# Motor_Controller.net
KiCad netlist of a schematic drawn in EAGLE
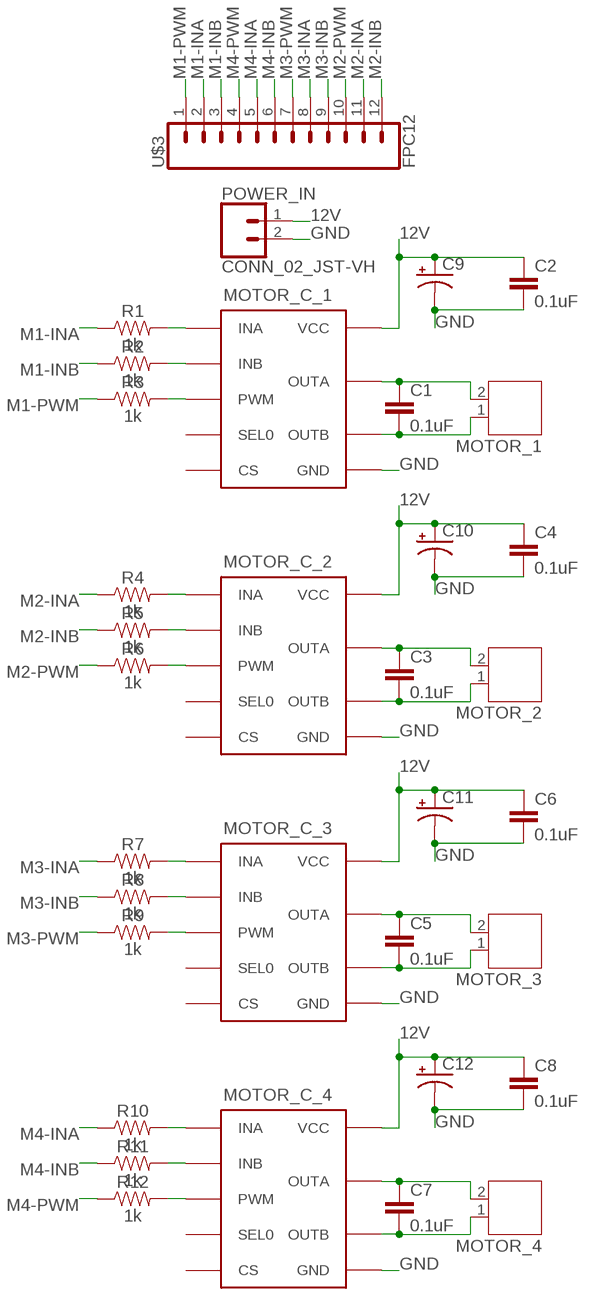
[diagram p0: schematic, sheet 1]

(export (version "E")
  (design (tool "Eeschema 10.0.6"))
  (components
    (comp (ref "C1")
      (value "0.1uF")
      (footprint "eagle-import:0603")
      (libsource (lib "eagle-import") (part "0.1UF-0603-25V-(+80/-20%)"))
    )
    (comp (ref "C2")
      (value "0.1uF")
      (footprint "eagle-import:0603")
      (libsource (lib "eagle-import") (part "0.1UF-0603-25V-(+80/-20%)"))
    )
    (comp (ref "C3")
      (value "0.1uF")
      (footprint "eagle-import:0603")
      (libsource (lib "eagle-import") (part "0.1UF-0603-25V-(+80/-20%)"))
    )
    (comp (ref "C4")
      (value "0.1uF")
      (footprint "eagle-import:0603")
      (libsource (lib "eagle-import") (part "0.1UF-0603-25V-(+80/-20%)"))
    )
    (comp (ref "C5")
      (value "0.1uF")
      (footprint "eagle-import:0603")
      (libsource (lib "eagle-import") (part "0.1UF-0603-25V-(+80/-20%)"))
    )
    (comp (ref "C6")
      (value "0.1uF")
      (footprint "eagle-import:0603")
      (libsource (lib "eagle-import") (part "0.1UF-0603-25V-(+80/-20%)"))
    )
    (comp (ref "C7")
      (value "0.1uF")
      (footprint "eagle-import:0603")
      (libsource (lib "eagle-import") (part "0.1UF-0603-25V-(+80/-20%)"))
    )
    (comp (ref "C8")
      (value "0.1uF")
      (footprint "eagle-import:0603")
      (libsource (lib "eagle-import") (part "0.1UF-0603-25V-(+80/-20%)"))
    )
    (comp (ref "C9")
      (value "CPOL-USE3.5-8")
      (footprint "eagle-import:E3,5-8")
      (libsource (lib "eagle-import") (part "CPOL-USE3.5-8"))
    )
    (comp (ref "C10")
      (value "CPOL-USE3.5-8")
      (footprint "eagle-import:E3,5-8")
      (libsource (lib "eagle-import") (part "CPOL-USE3.5-8"))
    )
    (comp (ref "C11")
      (value "CPOL-USE3.5-8")
      (footprint "eagle-import:E3,5-8")
      (libsource (lib "eagle-import") (part "CPOL-USE3.5-8"))
    )
    (comp (ref "C12")
      (value "CPOL-USE3.5-8")
      (footprint "eagle-import:E3,5-8")
      (libsource (lib "eagle-import") (part "CPOL-USE3.5-8"))
    )
    (comp (ref "MOTOR_1")
      (value "JST-PH2")
      (footprint "eagle-import:JST-PH2")
      (libsource (lib "eagle-import") (part "JST-PH2"))
    )
    (comp (ref "MOTOR_2")
      (value "JST-PH2")
      (footprint "eagle-import:JST-PH2")
      (libsource (lib "eagle-import") (part "JST-PH2"))
    )
    (comp (ref "MOTOR_3")
      (value "JST-PH2")
      (footprint "eagle-import:JST-PH2")
      (libsource (lib "eagle-import") (part "JST-PH2"))
    )
    (comp (ref "MOTOR_4")
      (value "JST-PH2")
      (footprint "eagle-import:JST-PH2")
      (libsource (lib "eagle-import") (part "JST-PH2"))
    )
    (comp (ref "MOTOR_C_1")
      (value "VNH7100BASTR")
      (footprint "eagle-import:SO-16")
      (libsource (lib "eagle-import") (part "VNH7100BASTR"))
    )
    (comp (ref "MOTOR_C_2")
      (value "VNH7100BASTR")
      (footprint "eagle-import:SO-16")
      (libsource (lib "eagle-import") (part "VNH7100BASTR"))
    )
    (comp (ref "MOTOR_C_3")
      (value "VNH7100BASTR")
      (footprint "eagle-import:SO-16")
      (libsource (lib "eagle-import") (part "VNH7100BASTR"))
    )
    (comp (ref "MOTOR_C_4")
      (value "VNH7100BASTR")
      (footprint "eagle-import:SO-16")
      (libsource (lib "eagle-import") (part "VNH7100BASTR"))
    )
    (comp (ref "POWER_IN")
      (value "CONN_02_JST-VH")
      (footprint "eagle-import:B2P-VH")
      (libsource (lib "eagle-import") (part "CONN_02_JST-VH"))
    )
    (comp (ref "R1")
      (value "1k")
      (footprint "eagle-import:0603")
      (libsource (lib "eagle-import") (part "1KOHM-0603-1/10W-1%"))
    )
    (comp (ref "R2")
      (value "1k")
      (footprint "eagle-import:0603")
      (libsource (lib "eagle-import") (part "1KOHM-0603-1/10W-1%"))
    )
    (comp (ref "R3")
      (value "1k")
      (footprint "eagle-import:0603")
      (libsource (lib "eagle-import") (part "1KOHM-0603-1/10W-1%"))
    )
    (comp (ref "R4")
      (value "1k")
      (footprint "eagle-import:0603")
      (libsource (lib "eagle-import") (part "1KOHM-0603-1/10W-1%"))
    )
    (comp (ref "R5")
      (value "1k")
      (footprint "eagle-import:0603")
      (libsource (lib "eagle-import") (part "1KOHM-0603-1/10W-1%"))
    )
    (comp (ref "R6")
      (value "1k")
      (footprint "eagle-import:0603")
      (libsource (lib "eagle-import") (part "1KOHM-0603-1/10W-1%"))
    )
    (comp (ref "R7")
      (value "1k")
      (footprint "eagle-import:0603")
      (libsource (lib "eagle-import") (part "1KOHM-0603-1/10W-1%"))
    )
    (comp (ref "R8")
      (value "1k")
      (footprint "eagle-import:0603")
      (libsource (lib "eagle-import") (part "1KOHM-0603-1/10W-1%"))
    )
    (comp (ref "R9")
      (value "1k")
      (footprint "eagle-import:0603")
      (libsource (lib "eagle-import") (part "1KOHM-0603-1/10W-1%"))
    )
    (comp (ref "R10")
      (value "1k")
      (footprint "eagle-import:0603")
      (libsource (lib "eagle-import") (part "1KOHM-0603-1/10W-1%"))
    )
    (comp (ref "R11")
      (value "1k")
      (footprint "eagle-import:0603")
      (libsource (lib "eagle-import") (part "1KOHM-0603-1/10W-1%"))
    )
    (comp (ref "R12")
      (value "1k")
      (footprint "eagle-import:0603")
      (libsource (lib "eagle-import") (part "1KOHM-0603-1/10W-1%"))
    )
    (comp (ref "U$3")
      (value "FPC12")
      (footprint "eagle-import:FPC12")
      (libsource (lib "eagle-import") (part "FPC12"))
    )
  )
  (nets
    (net (code "1") (name "/12V") (class "Default")
      (node (ref "C10") (pin "+") (pinfunction "+_+") (pintype "passive"))
      (node (ref "C11") (pin "+") (pinfunction "+_+") (pintype "passive"))
      (node (ref "C12") (pin "+") (pinfunction "+_+") (pintype "passive"))
      (node (ref "C2") (pin "1") (pinfunction "1_1") (pintype "passive"))
      (node (ref "C4") (pin "1") (pinfunction "1_1") (pintype "passive"))
      (node (ref "C6") (pin "1") (pinfunction "1_1") (pintype "passive"))
      (node (ref "C8") (pin "1") (pinfunction "1_1") (pintype "passive"))
      (node (ref "C9") (pin "+") (pinfunction "+_+") (pintype "passive"))
      (node (ref "MOTOR_C_1") (pin "12") (pinfunction "VCC_12") (pintype "bidirectional"))
      (node (ref "MOTOR_C_1") (pin "4") (pinfunction "VCC_4") (pintype "bidirectional"))
      (node (ref "MOTOR_C_1") (pin "5") (pinfunction "VCC_5") (pintype "bidirectional"))
      (node (ref "MOTOR_C_2") (pin "12") (pinfunction "VCC_12") (pintype "bidirectional"))
      (node (ref "MOTOR_C_2") (pin "4") (pinfunction "VCC_4") (pintype "bidirectional"))
      (node (ref "MOTOR_C_2") (pin "5") (pinfunction "VCC_5") (pintype "bidirectional"))
      (node (ref "MOTOR_C_3") (pin "12") (pinfunction "VCC_12") (pintype "bidirectional"))
      (node (ref "MOTOR_C_3") (pin "4") (pinfunction "VCC_4") (pintype "bidirectional"))
      (node (ref "MOTOR_C_3") (pin "5") (pinfunction "VCC_5") (pintype "bidirectional"))
      (node (ref "MOTOR_C_4") (pin "12") (pinfunction "VCC_12") (pintype "bidirectional"))
      (node (ref "MOTOR_C_4") (pin "4") (pinfunction "VCC_4") (pintype "bidirectional"))
      (node (ref "MOTOR_C_4") (pin "5") (pinfunction "VCC_5") (pintype "bidirectional"))
      (node (ref "POWER_IN") (pin "1") (pinfunction "1_1") (pintype "passive"))
    )
    (net (code "2") (name "/GND") (class "Default")
      (node (ref "C10") (pin "-") (pinfunction "-_-") (pintype "passive"))
      (node (ref "C11") (pin "-") (pinfunction "-_-") (pintype "passive"))
      (node (ref "C12") (pin "-") (pinfunction "-_-") (pintype "passive"))
      (node (ref "C2") (pin "2") (pinfunction "2_2") (pintype "passive"))
      (node (ref "C4") (pin "2") (pinfunction "2_2") (pintype "passive"))
      (node (ref "C6") (pin "2") (pinfunction "2_2") (pintype "passive"))
      (node (ref "C8") (pin "2") (pinfunction "2_2") (pintype "passive"))
      (node (ref "C9") (pin "-") (pinfunction "-_-") (pintype "passive"))
      (node (ref "MOTOR_C_1") (pin "1") (pinfunction "GND_1") (pintype "bidirectional"))
      (node (ref "MOTOR_C_1") (pin "16") (pinfunction "GND_16") (pintype "bidirectional"))
      (node (ref "MOTOR_C_1") (pin "8") (pinfunction "GND_8") (pintype "bidirectional"))
      (node (ref "MOTOR_C_1") (pin "9") (pinfunction "GND_9") (pintype "bidirectional"))
      (node (ref "MOTOR_C_2") (pin "1") (pinfunction "GND_1") (pintype "bidirectional"))
      (node (ref "MOTOR_C_2") (pin "16") (pinfunction "GND_16") (pintype "bidirectional"))
      (node (ref "MOTOR_C_2") (pin "8") (pinfunction "GND_8") (pintype "bidirectional"))
      (node (ref "MOTOR_C_2") (pin "9") (pinfunction "GND_9") (pintype "bidirectional"))
      (node (ref "MOTOR_C_3") (pin "1") (pinfunction "GND_1") (pintype "bidirectional"))
      (node (ref "MOTOR_C_3") (pin "16") (pinfunction "GND_16") (pintype "bidirectional"))
      (node (ref "MOTOR_C_3") (pin "8") (pinfunction "GND_8") (pintype "bidirectional"))
      (node (ref "MOTOR_C_3") (pin "9") (pinfunction "GND_9") (pintype "bidirectional"))
      (node (ref "MOTOR_C_4") (pin "1") (pinfunction "GND_1") (pintype "bidirectional"))
      (node (ref "MOTOR_C_4") (pin "16") (pinfunction "GND_16") (pintype "bidirectional"))
      (node (ref "MOTOR_C_4") (pin "8") (pinfunction "GND_8") (pintype "bidirectional"))
      (node (ref "MOTOR_C_4") (pin "9") (pinfunction "GND_9") (pintype "bidirectional"))
      (node (ref "POWER_IN") (pin "2") (pinfunction "2_2") (pintype "passive"))
    )
    (net (code "3") (name "/M1-INA") (class "Default")
      (node (ref "R1") (pin "1") (pinfunction "1_1") (pintype "passive"))
      (node (ref "U$3") (pin "2") (pinfunction "2_2") (pintype "passive"))
    )
    (net (code "4") (name "/M1-INB") (class "Default")
      (node (ref "R2") (pin "1") (pinfunction "1_1") (pintype "passive"))
      (node (ref "U$3") (pin "3") (pinfunction "3_3") (pintype "passive"))
    )
    (net (code "5") (name "/M1-PWM") (class "Default")
      (node (ref "R3") (pin "1") (pinfunction "1_1") (pintype "passive"))
      (node (ref "U$3") (pin "1") (pinfunction "1_1") (pintype "passive"))
    )
    (net (code "6") (name "/M2-INA") (class "Default")
      (node (ref "R4") (pin "1") (pinfunction "1_1") (pintype "passive"))
      (node (ref "U$3") (pin "11") (pinfunction "11_11") (pintype "passive"))
    )
    (net (code "7") (name "/M2-INB") (class "Default")
      (node (ref "R5") (pin "1") (pinfunction "1_1") (pintype "passive"))
      (node (ref "U$3") (pin "12") (pinfunction "12_12") (pintype "passive"))
    )
    (net (code "8") (name "/M2-PWM") (class "Default")
      (node (ref "R6") (pin "1") (pinfunction "1_1") (pintype "passive"))
      (node (ref "U$3") (pin "10") (pinfunction "10_10") (pintype "passive"))
    )
    (net (code "9") (name "/M3-INA") (class "Default")
      (node (ref "R7") (pin "1") (pinfunction "1_1") (pintype "passive"))
      (node (ref "U$3") (pin "8") (pinfunction "8_8") (pintype "passive"))
    )
    (net (code "10") (name "/M3-INB") (class "Default")
      (node (ref "R8") (pin "1") (pinfunction "1_1") (pintype "passive"))
      (node (ref "U$3") (pin "9") (pinfunction "9_9") (pintype "passive"))
    )
    (net (code "11") (name "/M3-PWM") (class "Default")
      (node (ref "R9") (pin "1") (pinfunction "1_1") (pintype "passive"))
      (node (ref "U$3") (pin "7") (pinfunction "7_7") (pintype "passive"))
    )
    (net (code "12") (name "/M4-INA") (class "Default")
      (node (ref "R10") (pin "1") (pinfunction "1_1") (pintype "passive"))
      (node (ref "U$3") (pin "5") (pinfunction "5_5") (pintype "passive"))
    )
    (net (code "13") (name "/M4-INB") (class "Default")
      (node (ref "R11") (pin "1") (pinfunction "1_1") (pintype "passive"))
      (node (ref "U$3") (pin "6") (pinfunction "6_6") (pintype "passive"))
    )
    (net (code "14") (name "/M4-PWM") (class "Default")
      (node (ref "R12") (pin "1") (pinfunction "1_1") (pintype "passive"))
      (node (ref "U$3") (pin "4") (pinfunction "4_4") (pintype "passive"))
    )
    (net (code "15") (name "Net-(C1-Pad1)") (class "Default")
      (node (ref "C1") (pin "1") (pinfunction "1_1") (pintype "passive"))
      (node (ref "MOTOR_1") (pin "2") (pinfunction "2_2") (pintype "passive"))
      (node (ref "MOTOR_C_1") (pin "15") (pinfunction "OUTA_15") (pintype "bidirectional"))
      (node (ref "MOTOR_C_1") (pin "2") (pinfunction "OUTA_2") (pintype "bidirectional"))
    )
    (net (code "16") (name "Net-(C1-Pad2)") (class "Default")
      (node (ref "C1") (pin "2") (pinfunction "2_2") (pintype "passive"))
      (node (ref "MOTOR_1") (pin "1") (pinfunction "1_1") (pintype "passive"))
      (node (ref "MOTOR_C_1") (pin "10") (pinfunction "OUTB_10") (pintype "bidirectional"))
      (node (ref "MOTOR_C_1") (pin "7") (pinfunction "OUTB_7") (pintype "bidirectional"))
    )
    (net (code "17") (name "Net-(C3-Pad1)") (class "Default")
      (node (ref "C3") (pin "1") (pinfunction "1_1") (pintype "passive"))
      (node (ref "MOTOR_2") (pin "2") (pinfunction "2_2") (pintype "passive"))
      (node (ref "MOTOR_C_2") (pin "15") (pinfunction "OUTA_15") (pintype "bidirectional"))
      (node (ref "MOTOR_C_2") (pin "2") (pinfunction "OUTA_2") (pintype "bidirectional"))
    )
    (net (code "18") (name "Net-(C3-Pad2)") (class "Default")
      (node (ref "C3") (pin "2") (pinfunction "2_2") (pintype "passive"))
      (node (ref "MOTOR_2") (pin "1") (pinfunction "1_1") (pintype "passive"))
      (node (ref "MOTOR_C_2") (pin "10") (pinfunction "OUTB_10") (pintype "bidirectional"))
      (node (ref "MOTOR_C_2") (pin "7") (pinfunction "OUTB_7") (pintype "bidirectional"))
    )
    (net (code "19") (name "Net-(C5-Pad1)") (class "Default")
      (node (ref "C5") (pin "1") (pinfunction "1_1") (pintype "passive"))
      (node (ref "MOTOR_3") (pin "2") (pinfunction "2_2") (pintype "passive"))
      (node (ref "MOTOR_C_3") (pin "15") (pinfunction "OUTA_15") (pintype "bidirectional"))
      (node (ref "MOTOR_C_3") (pin "2") (pinfunction "OUTA_2") (pintype "bidirectional"))
    )
    (net (code "20") (name "Net-(C5-Pad2)") (class "Default")
      (node (ref "C5") (pin "2") (pinfunction "2_2") (pintype "passive"))
      (node (ref "MOTOR_3") (pin "1") (pinfunction "1_1") (pintype "passive"))
      (node (ref "MOTOR_C_3") (pin "10") (pinfunction "OUTB_10") (pintype "bidirectional"))
      (node (ref "MOTOR_C_3") (pin "7") (pinfunction "OUTB_7") (pintype "bidirectional"))
    )
    (net (code "21") (name "Net-(C7-Pad1)") (class "Default")
      (node (ref "C7") (pin "1") (pinfunction "1_1") (pintype "passive"))
      (node (ref "MOTOR_4") (pin "2") (pinfunction "2_2") (pintype "passive"))
      (node (ref "MOTOR_C_4") (pin "15") (pinfunction "OUTA_15") (pintype "bidirectional"))
      (node (ref "MOTOR_C_4") (pin "2") (pinfunction "OUTA_2") (pintype "bidirectional"))
    )
    (net (code "22") (name "Net-(C7-Pad2)") (class "Default")
      (node (ref "C7") (pin "2") (pinfunction "2_2") (pintype "passive"))
      (node (ref "MOTOR_4") (pin "1") (pinfunction "1_1") (pintype "passive"))
      (node (ref "MOTOR_C_4") (pin "10") (pinfunction "OUTB_10") (pintype "bidirectional"))
      (node (ref "MOTOR_C_4") (pin "7") (pinfunction "OUTB_7") (pintype "bidirectional"))
    )
    (net (code "23") (name "Net-(MOTOR_C_1-INA)") (class "Default")
      (node (ref "MOTOR_C_1") (pin "3") (pinfunction "INA_3") (pintype "bidirectional"))
      (node (ref "R1") (pin "2") (pinfunction "2_2") (pintype "passive"))
    )
    (net (code "24") (name "Net-(MOTOR_C_1-INB)") (class "Default")
      (node (ref "MOTOR_C_1") (pin "6") (pinfunction "INB_6") (pintype "bidirectional"))
      (node (ref "R2") (pin "2") (pinfunction "2_2") (pintype "passive"))
    )
    (net (code "25") (name "Net-(MOTOR_C_1-PWM)") (class "Default")
      (node (ref "MOTOR_C_1") (pin "11") (pinfunction "PWM_11") (pintype "bidirectional"))
      (node (ref "R3") (pin "2") (pinfunction "2_2") (pintype "passive"))
    )
    (net (code "26") (name "Net-(MOTOR_C_2-INA)") (class "Default")
      (node (ref "MOTOR_C_2") (pin "3") (pinfunction "INA_3") (pintype "bidirectional"))
      (node (ref "R4") (pin "2") (pinfunction "2_2") (pintype "passive"))
    )
    (net (code "27") (name "Net-(MOTOR_C_2-INB)") (class "Default")
      (node (ref "MOTOR_C_2") (pin "6") (pinfunction "INB_6") (pintype "bidirectional"))
      (node (ref "R5") (pin "2") (pinfunction "2_2") (pintype "passive"))
    )
    (net (code "28") (name "Net-(MOTOR_C_2-PWM)") (class "Default")
      (node (ref "MOTOR_C_2") (pin "11") (pinfunction "PWM_11") (pintype "bidirectional"))
      (node (ref "R6") (pin "2") (pinfunction "2_2") (pintype "passive"))
    )
    (net (code "29") (name "Net-(MOTOR_C_3-INA)") (class "Default")
      (node (ref "MOTOR_C_3") (pin "3") (pinfunction "INA_3") (pintype "bidirectional"))
      (node (ref "R7") (pin "2") (pinfunction "2_2") (pintype "passive"))
    )
    (net (code "30") (name "Net-(MOTOR_C_3-INB)") (class "Default")
      (node (ref "MOTOR_C_3") (pin "6") (pinfunction "INB_6") (pintype "bidirectional"))
      (node (ref "R8") (pin "2") (pinfunction "2_2") (pintype "passive"))
    )
    (net (code "31") (name "Net-(MOTOR_C_3-PWM)") (class "Default")
      (node (ref "MOTOR_C_3") (pin "11") (pinfunction "PWM_11") (pintype "bidirectional"))
      (node (ref "R9") (pin "2") (pinfunction "2_2") (pintype "passive"))
    )
    (net (code "32") (name "Net-(MOTOR_C_4-INA)") (class "Default")
      (node (ref "MOTOR_C_4") (pin "3") (pinfunction "INA_3") (pintype "bidirectional"))
      (node (ref "R10") (pin "2") (pinfunction "2_2") (pintype "passive"))
    )
    (net (code "33") (name "Net-(MOTOR_C_4-INB)") (class "Default")
      (node (ref "MOTOR_C_4") (pin "6") (pinfunction "INB_6") (pintype "bidirectional"))
      (node (ref "R11") (pin "2") (pinfunction "2_2") (pintype "passive"))
    )
    (net (code "34") (name "Net-(MOTOR_C_4-PWM)") (class "Default")
      (node (ref "MOTOR_C_4") (pin "11") (pinfunction "PWM_11") (pintype "bidirectional"))
      (node (ref "R12") (pin "2") (pinfunction "2_2") (pintype "passive"))
    )
    (net (code "35") (name "unconnected-(MOTOR_C_1-CS-Pad13)") (class "Default")
      (node (ref "MOTOR_C_1") (pin "13") (pinfunction "CS_13") (pintype "bidirectional"))
    )
    (net (code "36") (name "unconnected-(MOTOR_C_1-SEL0-Pad14)") (class "Default")
      (node (ref "MOTOR_C_1") (pin "14") (pinfunction "SEL0_14") (pintype "bidirectional"))
    )
    (net (code "37") (name "unconnected-(MOTOR_C_2-CS-Pad13)") (class "Default")
      (node (ref "MOTOR_C_2") (pin "13") (pinfunction "CS_13") (pintype "bidirectional"))
    )
    (net (code "38") (name "unconnected-(MOTOR_C_2-SEL0-Pad14)") (class "Default")
      (node (ref "MOTOR_C_2") (pin "14") (pinfunction "SEL0_14") (pintype "bidirectional"))
    )
    (net (code "39") (name "unconnected-(MOTOR_C_3-CS-Pad13)") (class "Default")
      (node (ref "MOTOR_C_3") (pin "13") (pinfunction "CS_13") (pintype "bidirectional"))
    )
    (net (code "40") (name "unconnected-(MOTOR_C_3-SEL0-Pad14)") (class "Default")
      (node (ref "MOTOR_C_3") (pin "14") (pinfunction "SEL0_14") (pintype "bidirectional"))
    )
    (net (code "41") (name "unconnected-(MOTOR_C_4-CS-Pad13)") (class "Default")
      (node (ref "MOTOR_C_4") (pin "13") (pinfunction "CS_13") (pintype "bidirectional"))
    )
    (net (code "42") (name "unconnected-(MOTOR_C_4-SEL0-Pad14)") (class "Default")
      (node (ref "MOTOR_C_4") (pin "14") (pinfunction "SEL0_14") (pintype "bidirectional"))
    )
  )
)
